# light_bulb2.net
KiCad netlist of a schematic drawn in EAGLE
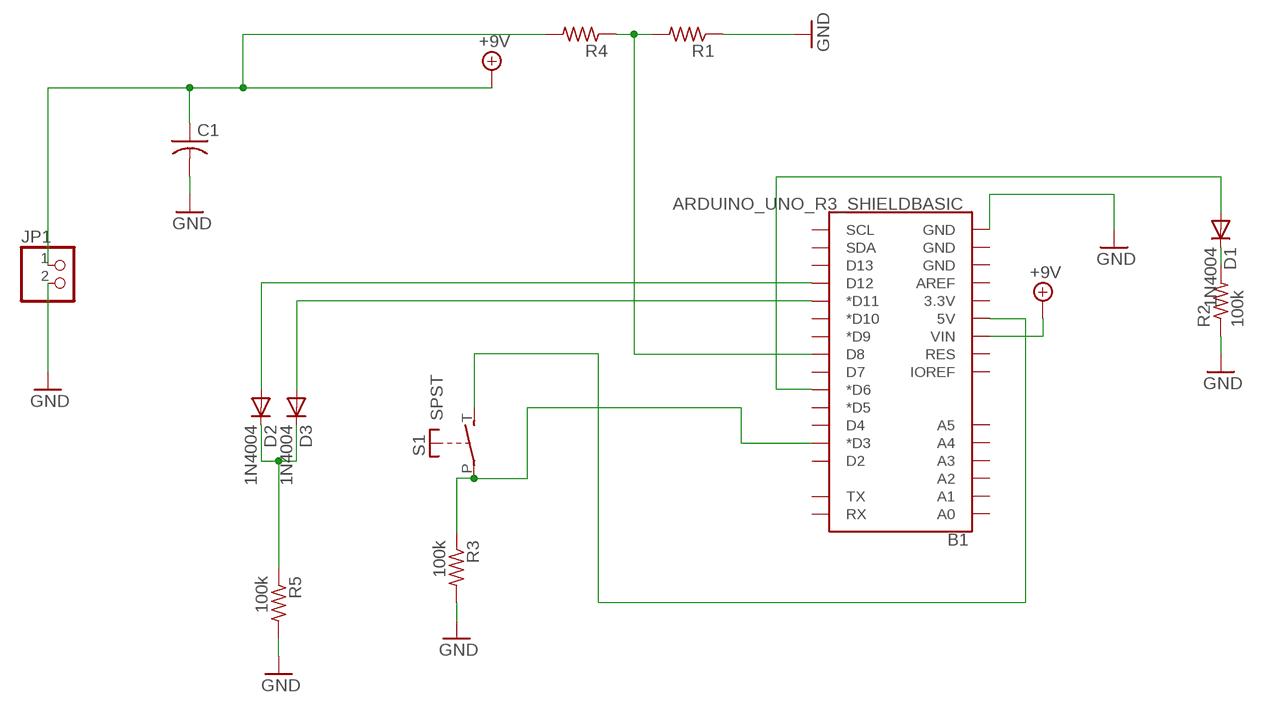
[diagram p0: schematic, sheet 1]

(export (version "E")
  (design (tool "Eeschema 10.0.6"))
  (components
    (comp (ref "B1")
      (value "ARDUINO_UNO_R3_SHIELDBASIC")
      (footprint "eagle-import:UNO_R3_SHIELD")
      (libsource (lib "eagle-import") (part "ARDUINO_UNO_R3_SHIELDBASIC"))
    )
    (comp (ref "C1")
      (value "0.1")
      (footprint "eagle-import:C0805")
      (libsource (lib "eagle-import") (part "C-USC0805"))
    )
    (comp (ref "D1")
      (value "1N4004")
      (footprint "eagle-import:DO41-10")
      (libsource (lib "eagle-import") (part "1N4004"))
    )
    (comp (ref "D2")
      (value "1N4004")
      (footprint "eagle-import:DO41-10")
      (libsource (lib "eagle-import") (part "1N4004"))
    )
    (comp (ref "D3")
      (value "1N4004")
      (footprint "eagle-import:DO41-10")
      (libsource (lib "eagle-import") (part "1N4004"))
    )
    (comp (ref "JP1")
      (value "PINHD-1X2")
      (footprint "eagle-import:1X02")
      (libsource (lib "eagle-import") (part "PINHD-1X2"))
    )
    (comp (ref "R1")
      (value "15k")
      (footprint "eagle-import:R0805")
      (libsource (lib "eagle-import") (part "R-US_R0805"))
    )
    (comp (ref "R2")
      (value "100k")
      (footprint "eagle-import:R0805")
      (libsource (lib "eagle-import") (part "R-US_R0805"))
    )
    (comp (ref "R3")
      (value "100k")
      (footprint "eagle-import:R0805")
      (libsource (lib "eagle-import") (part "R-US_R0805"))
    )
    (comp (ref "R4")
      (value "20k")
      (footprint "eagle-import:R0805")
      (libsource (lib "eagle-import") (part "R-US_R0805"))
    )
    (comp (ref "R5")
      (value "100k")
      (footprint "eagle-import:R0805")
      (libsource (lib "eagle-import") (part "R-US_R0805"))
    )
    (comp (ref "S1")
      (value "SPST")
      (footprint "eagle-import:JUDCOSPST")
      (libsource (lib "eagle-import") (part "SPST"))
    )
  )
  (nets
    (net (code "1") (name "+9V") (class "Default")
      (node (ref "B1") (pin "VIN") (pinfunction "VIN_VIN") (pintype "bidirectional"))
      (node (ref "C1") (pin "1") (pinfunction "1_1") (pintype "passive"))
      (node (ref "JP1") (pin "1") (pinfunction "1_1") (pintype "passive"))
      (node (ref "R4") (pin "2") (pinfunction "2_2") (pintype "passive"))
    )
    (net (code "2") (name "GND") (class "Default")
      (node (ref "B1") (pin "GND@0") (pinfunction "GND_GND@0") (pintype "bidirectional"))
      (node (ref "C1") (pin "2") (pinfunction "2_2") (pintype "passive"))
      (node (ref "JP1") (pin "2") (pinfunction "2_2") (pintype "passive"))
      (node (ref "R1") (pin "1") (pinfunction "1_1") (pintype "passive"))
      (node (ref "R2") (pin "1") (pinfunction "1_1") (pintype "passive"))
      (node (ref "R3") (pin "2") (pinfunction "2_2") (pintype "passive"))
      (node (ref "R5") (pin "2") (pinfunction "2_2") (pintype "passive"))
    )
    (net (code "3") (name "Net-(B1-*D3)") (class "Default")
      (node (ref "B1") (pin "D3") (pinfunction "*D3_D3") (pintype "bidirectional"))
      (node (ref "R3") (pin "1") (pinfunction "1_1") (pintype "passive"))
      (node (ref "S1") (pin "P") (pinfunction "P_P") (pintype "passive"))
    )
    (net (code "4") (name "Net-(B1-*D6)") (class "Default")
      (node (ref "B1") (pin "D6") (pinfunction "*D6_D6") (pintype "bidirectional"))
      (node (ref "D1") (pin "A") (pinfunction "A_A") (pintype "passive"))
    )
    (net (code "5") (name "Net-(B1-*D11)") (class "Default")
      (node (ref "B1") (pin "D11") (pinfunction "*D11_D11") (pintype "bidirectional"))
      (node (ref "D3") (pin "A") (pinfunction "A_A") (pintype "passive"))
    )
    (net (code "6") (name "Net-(B1-PadD8)") (class "Default")
      (node (ref "B1") (pin "D8") (pinfunction "D8_D8") (pintype "bidirectional"))
      (node (ref "R1") (pin "2") (pinfunction "2_2") (pintype "passive"))
      (node (ref "R4") (pin "1") (pinfunction "1_1") (pintype "passive"))
    )
    (net (code "7") (name "Net-(B1-PadD12)") (class "Default")
      (node (ref "B1") (pin "D12") (pinfunction "D12_D12") (pintype "bidirectional"))
      (node (ref "D2") (pin "A") (pinfunction "A_A") (pintype "passive"))
    )
    (net (code "8") (name "Net-(D1-PadC)") (class "Default")
      (node (ref "D1") (pin "C") (pinfunction "C_C") (pintype "passive"))
      (node (ref "R2") (pin "2") (pinfunction "2_2") (pintype "passive"))
    )
    (net (code "9") (name "Net-(D2-PadC)") (class "Default")
      (node (ref "D2") (pin "C") (pinfunction "C_C") (pintype "passive"))
      (node (ref "D3") (pin "C") (pinfunction "C_C") (pintype "passive"))
      (node (ref "R5") (pin "1") (pinfunction "1_1") (pintype "passive"))
    )
    (net (code "10") (name "Net-(S1-S)") (class "Default")
      (node (ref "B1") (pin "5V") (pinfunction "5V_5V") (pintype "bidirectional"))
      (node (ref "S1") (pin "T") (pinfunction "S_T") (pintype "passive"))
    )
    (net (code "11") (name "unconnected-(B1-*D5-PadD5)") (class "Default")
      (node (ref "B1") (pin "D5") (pinfunction "*D5_D5") (pintype "bidirectional"))
    )
    (net (code "12") (name "unconnected-(B1-*D9-PadD9)") (class "Default")
      (node (ref "B1") (pin "D9") (pinfunction "*D9_D9") (pintype "bidirectional"))
    )
    (net (code "13") (name "unconnected-(B1-*D10-PadD10)") (class "Default")
      (node (ref "B1") (pin "D10") (pinfunction "*D10_D10") (pintype "bidirectional"))
    )
    (net (code "14") (name "unconnected-(B1-GND-PadGND@1)") (class "Default")
      (node (ref "B1") (pin "GND@1") (pinfunction "GND_GND@1") (pintype "bidirectional"))
    )
    (net (code "15") (name "unconnected-(B1-GND-PadGND@2)") (class "Default")
      (node (ref "B1") (pin "GND@2") (pinfunction "GND_GND@2") (pintype "bidirectional"))
    )
    (net (code "16") (name "unconnected-(B1-Pad3.3V)") (class "Default")
      (node (ref "B1") (pin "3.3V") (pinfunction "3.3V_3.3V") (pintype "bidirectional"))
    )
    (net (code "17") (name "unconnected-(B1-PadA0)") (class "Default")
      (node (ref "B1") (pin "A0") (pinfunction "A0_A0") (pintype "bidirectional"))
    )
    (net (code "18") (name "unconnected-(B1-PadA1)") (class "Default")
      (node (ref "B1") (pin "A1") (pinfunction "A1_A1") (pintype "bidirectional"))
    )
    (net (code "19") (name "unconnected-(B1-PadA2)") (class "Default")
      (node (ref "B1") (pin "A2") (pinfunction "A2_A2") (pintype "bidirectional"))
    )
    (net (code "20") (name "unconnected-(B1-PadA3)") (class "Default")
      (node (ref "B1") (pin "A3") (pinfunction "A3_A3") (pintype "bidirectional"))
    )
    (net (code "21") (name "unconnected-(B1-PadA4)") (class "Default")
      (node (ref "B1") (pin "A4") (pinfunction "A4_A4") (pintype "bidirectional"))
    )
    (net (code "22") (name "unconnected-(B1-PadA5)") (class "Default")
      (node (ref "B1") (pin "A5") (pinfunction "A5_A5") (pintype "bidirectional"))
    )
    (net (code "23") (name "unconnected-(B1-PadAREF)") (class "Default")
      (node (ref "B1") (pin "AREF") (pinfunction "AREF_AREF") (pintype "bidirectional"))
    )
    (net (code "24") (name "unconnected-(B1-PadD2)") (class "Default")
      (node (ref "B1") (pin "D2") (pinfunction "D2_D2") (pintype "bidirectional"))
    )
    (net (code "25") (name "unconnected-(B1-PadD4)") (class "Default")
      (node (ref "B1") (pin "D4") (pinfunction "D4_D4") (pintype "bidirectional"))
    )
    (net (code "26") (name "unconnected-(B1-PadD7)") (class "Default")
      (node (ref "B1") (pin "D7") (pinfunction "D7_D7") (pintype "bidirectional"))
    )
    (net (code "27") (name "unconnected-(B1-PadD13)") (class "Default")
      (node (ref "B1") (pin "D13") (pinfunction "D13_D13") (pintype "bidirectional"))
    )
    (net (code "28") (name "unconnected-(B1-PadIOREF)") (class "Default")
      (node (ref "B1") (pin "IOREF") (pinfunction "IOREF_IOREF") (pintype "bidirectional"))
    )
    (net (code "29") (name "unconnected-(B1-PadRES)") (class "Default")
      (node (ref "B1") (pin "RES") (pinfunction "RES_RES") (pintype "bidirectional"))
    )
    (net (code "30") (name "unconnected-(B1-PadRX)") (class "Default")
      (node (ref "B1") (pin "RX") (pinfunction "RX_RX") (pintype "bidirectional"))
    )
    (net (code "31") (name "unconnected-(B1-PadSCL)") (class "Default")
      (node (ref "B1") (pin "SCL") (pinfunction "SCL_SCL") (pintype "bidirectional"))
    )
    (net (code "32") (name "unconnected-(B1-PadSDA)") (class "Default")
      (node (ref "B1") (pin "SDA") (pinfunction "SDA_SDA") (pintype "bidirectional"))
    )
    (net (code "33") (name "unconnected-(B1-PadTX)") (class "Default")
      (node (ref "B1") (pin "TX") (pinfunction "TX_TX") (pintype "bidirectional"))
    )
  )
)
